# ADC.net
KiCad netlist of a schematic drawn in Altium Designer
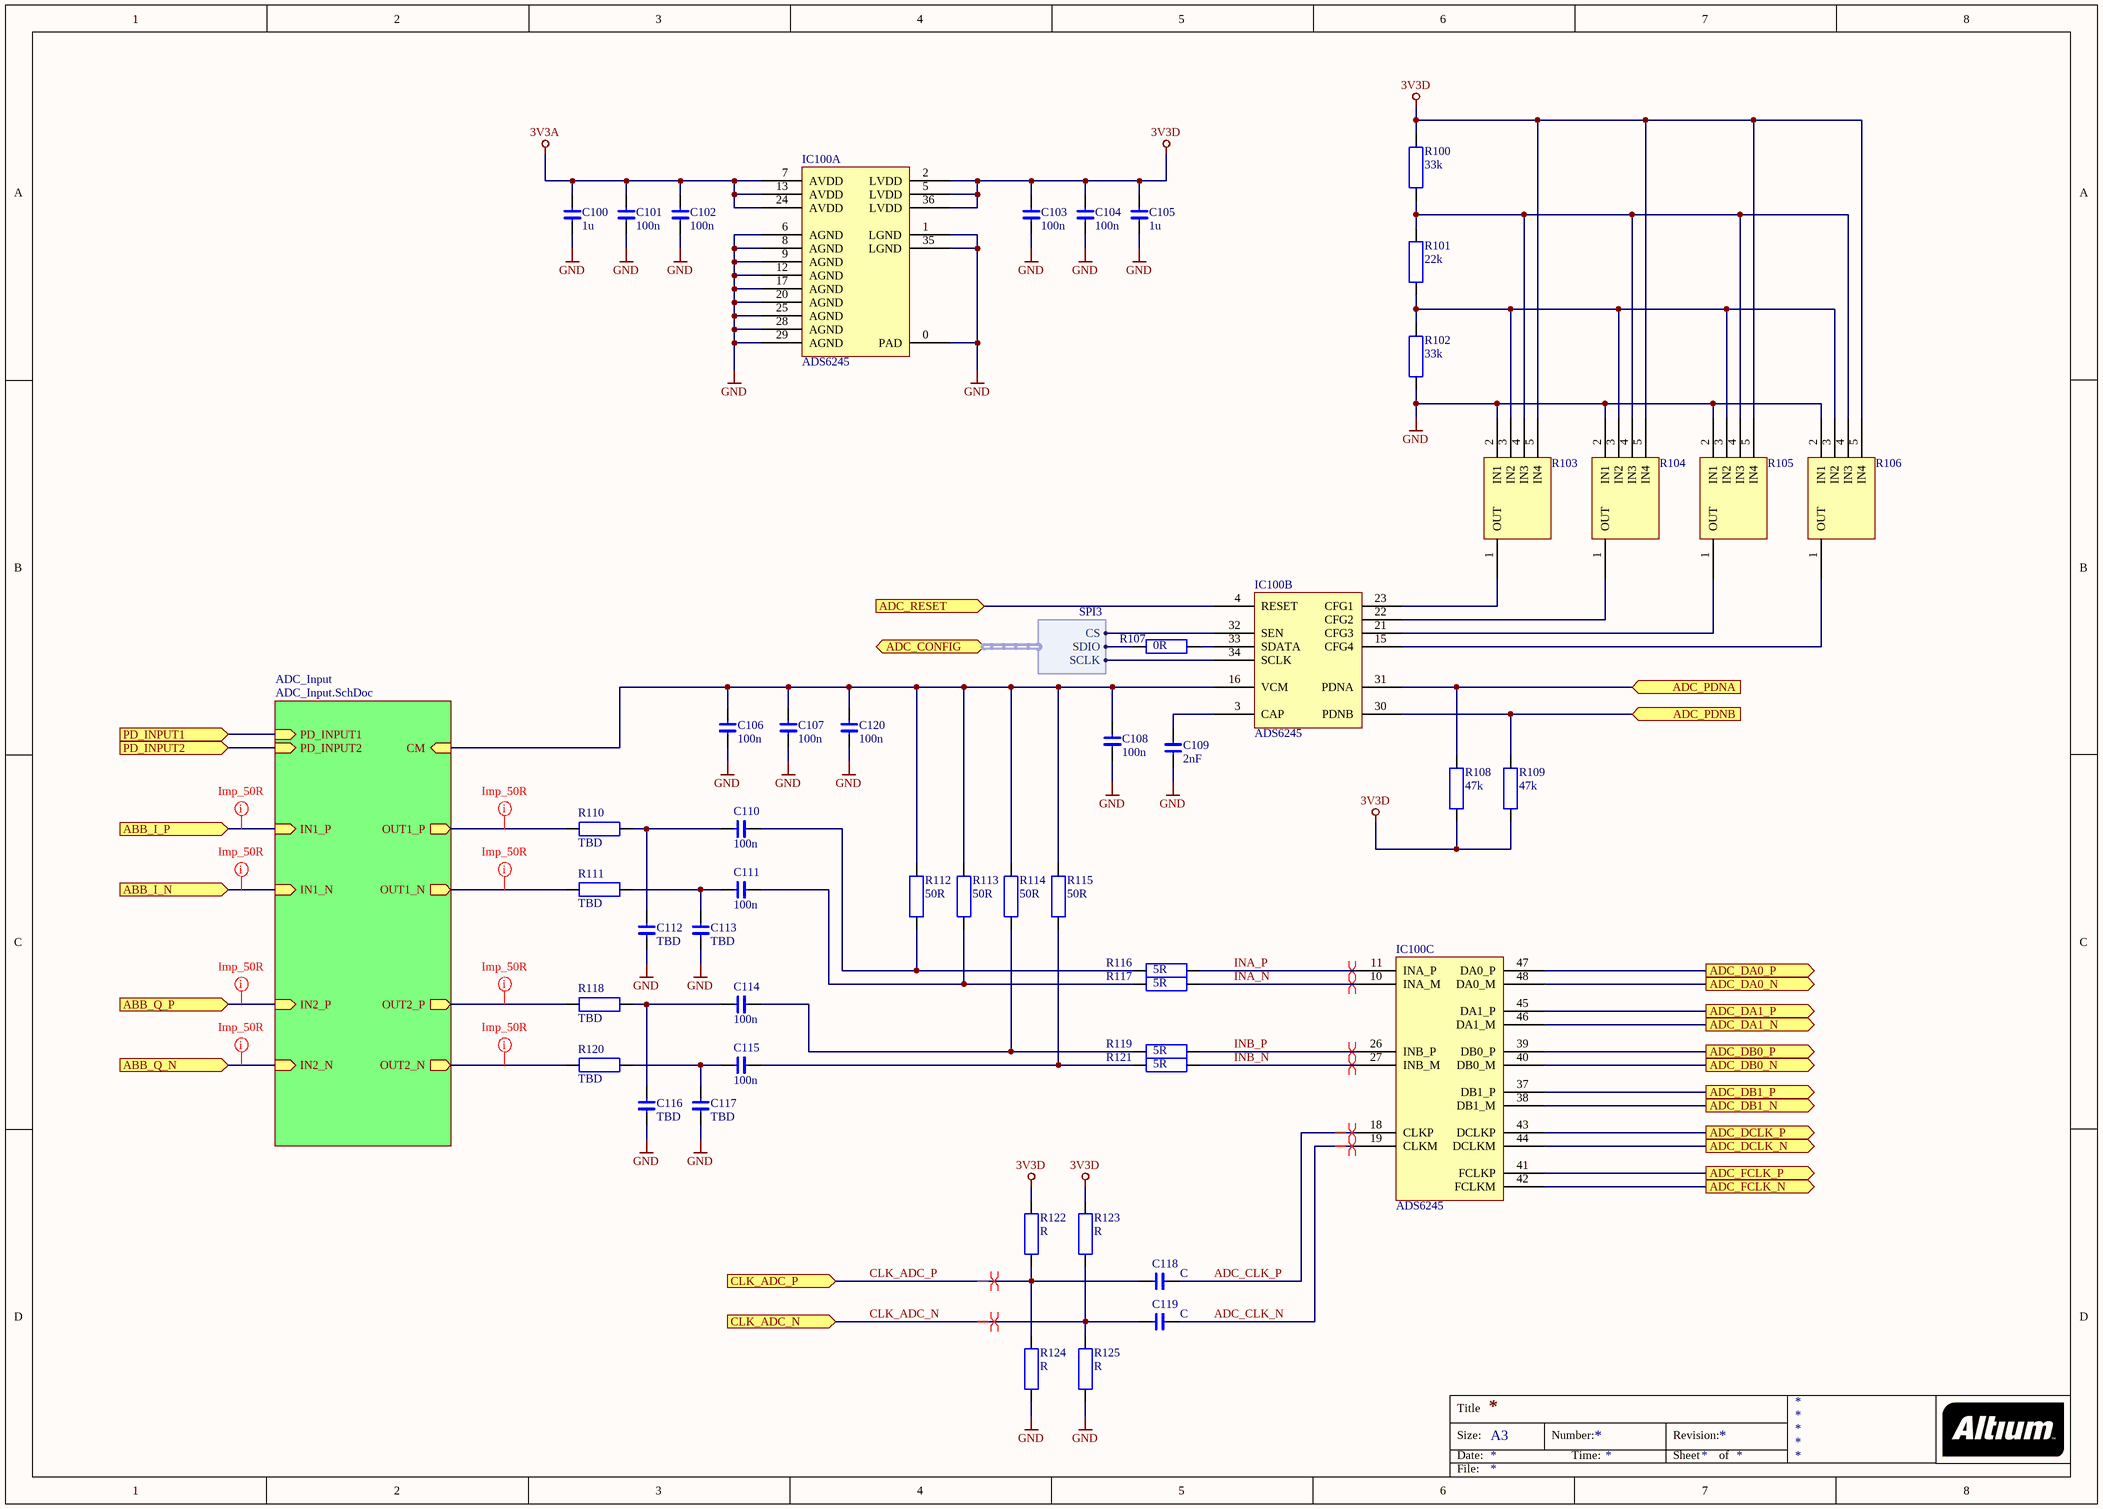
[diagram p0: ADC.SchDoc]

(export (version "E")
  (design (tool "Eeschema 10.0.6"))
  (components
    (comp (ref "C100")
      (value "1u")
      (footprint "0603 SMALL OUTLINE")
      (description "C")
      (libsource (lib "RCL") (part "C"))
    )
    (comp (ref "C101")
      (value "100n")
      (footprint "0603 SMALL OUTLINE")
      (description "C")
      (libsource (lib "RCL") (part "C"))
    )
    (comp (ref "C102")
      (value "100n")
      (footprint "0603 SMALL OUTLINE")
      (description "C")
      (libsource (lib "RCL") (part "C"))
    )
    (comp (ref "C103")
      (value "100n")
      (footprint "0603 SMALL OUTLINE")
      (description "C")
      (libsource (lib "RCL") (part "C"))
    )
    (comp (ref "C104")
      (value "100n")
      (footprint "0603 SMALL OUTLINE")
      (description "C")
      (libsource (lib "RCL") (part "C"))
    )
    (comp (ref "C105")
      (value "1u")
      (footprint "0603 SMALL OUTLINE")
      (description "C")
      (libsource (lib "RCL") (part "C"))
    )
    (comp (ref "C106")
      (value "100n")
      (footprint "0603 SMALL OUTLINE")
      (description "C")
      (libsource (lib "RCL") (part "C"))
    )
    (comp (ref "C107")
      (value "100n")
      (footprint "0603 SMALL OUTLINE")
      (description "C")
      (libsource (lib "RCL") (part "C"))
    )
    (comp (ref "C108")
      (value "100n")
      (footprint "0603 SMALL OUTLINE")
      (description "C")
      (libsource (lib "RCL") (part "C"))
    )
    (comp (ref "C109")
      (value "2nF")
      (footprint "0603 SMALL OUTLINE")
      (description "C")
      (libsource (lib "RCL") (part "C"))
    )
    (comp (ref "C110")
      (value "100n")
      (footprint "0603 SMALL OUTLINE")
      (description "C")
      (libsource (lib "RCL") (part "C"))
    )
    (comp (ref "C111")
      (value "100n")
      (footprint "0603 SMALL OUTLINE")
      (description "C")
      (libsource (lib "RCL") (part "C"))
    )
    (comp (ref "C112")
      (value "TBD")
      (footprint "0603 SMALL OUTLINE")
      (description "C")
      (libsource (lib "RCL") (part "C"))
    )
    (comp (ref "C113")
      (value "TBD")
      (footprint "0603 SMALL OUTLINE")
      (description "C")
      (libsource (lib "RCL") (part "C"))
    )
    (comp (ref "C114")
      (value "100n")
      (footprint "0603 SMALL OUTLINE")
      (description "C")
      (libsource (lib "RCL") (part "C"))
    )
    (comp (ref "C115")
      (value "100n")
      (footprint "0603 SMALL OUTLINE")
      (description "C")
      (libsource (lib "RCL") (part "C"))
    )
    (comp (ref "C116")
      (value "TBD")
      (footprint "0603 SMALL OUTLINE")
      (description "C")
      (libsource (lib "RCL") (part "C"))
    )
    (comp (ref "C117")
      (value "TBD")
      (footprint "0603 SMALL OUTLINE")
      (description "C")
      (libsource (lib "RCL") (part "C"))
    )
    (comp (ref "C118") (value "C") (footprint "0603 SMALL OUTLINE") (libsource (lib "RCL") (part "C")))
    (comp (ref "C119") (value "C") (footprint "0603 SMALL OUTLINE") (libsource (lib "RCL") (part "C")))
    (comp (ref "C120")
      (value "100n")
      (footprint "0603 SMALL OUTLINE")
      (description "C")
      (libsource (lib "RCL") (part "C"))
    )
    (comp (ref "IC100")
      (value "ADS6245")
      (footprint "VQFN48_LONG")
      (description "DUAL CHANNEL, 14-BIT, 125/105/80/65 MSPS ADC WITH SERIAL LVDS OUTPUTS")
      (libsource (lib "Private") (part "ADS6245_2WIRE"))
    )
    (comp (ref "R100")
      (value "33k")
      (footprint "0603 SMALL OUTLINE")
      (description "R")
      (libsource (lib "RCL") (part "R"))
    )
    (comp (ref "R101")
      (value "22k")
      (footprint "0603 SMALL OUTLINE")
      (description "R")
      (libsource (lib "RCL") (part "R"))
    )
    (comp (ref "R102")
      (value "33k")
      (footprint "0603 SMALL OUTLINE")
      (description "R")
      (libsource (lib "RCL") (part "R"))
    )
    (comp (ref "R103")
      (value "0603_MUX4")
      (footprint "0603_MUX4")
      (libsource (lib "Private") (part "0603_MUX4"))
    )
    (comp (ref "R104")
      (value "0603_MUX4")
      (footprint "0603_MUX4")
      (libsource (lib "Private") (part "0603_MUX4"))
    )
    (comp (ref "R105")
      (value "0603_MUX4")
      (footprint "0603_MUX4")
      (libsource (lib "Private") (part "0603_MUX4"))
    )
    (comp (ref "R106")
      (value "0603_MUX4")
      (footprint "0603_MUX4")
      (libsource (lib "Private") (part "0603_MUX4"))
    )
    (comp (ref "R107")
      (value "0R")
      (footprint "0603 SMALL OUTLINE")
      (description "R")
      (libsource (lib "RCL") (part "R"))
    )
    (comp (ref "R108")
      (value "47k")
      (footprint "0603 SMALL OUTLINE")
      (description "R")
      (libsource (lib "RCL") (part "R"))
    )
    (comp (ref "R109")
      (value "47k")
      (footprint "0603 SMALL OUTLINE")
      (description "R")
      (libsource (lib "RCL") (part "R"))
    )
    (comp (ref "R110")
      (value "TBD")
      (footprint "0603 SMALL OUTLINE")
      (description "R")
      (libsource (lib "RCL") (part "R"))
    )
    (comp (ref "R111")
      (value "TBD")
      (footprint "0603 SMALL OUTLINE")
      (description "R")
      (libsource (lib "RCL") (part "R"))
    )
    (comp (ref "R112")
      (value "50R")
      (footprint "0603 SMALL OUTLINE")
      (description "R")
      (libsource (lib "RCL") (part "R"))
    )
    (comp (ref "R113")
      (value "50R")
      (footprint "0603 SMALL OUTLINE")
      (description "R")
      (libsource (lib "RCL") (part "R"))
    )
    (comp (ref "R114")
      (value "50R")
      (footprint "0603 SMALL OUTLINE")
      (description "R")
      (libsource (lib "RCL") (part "R"))
    )
    (comp (ref "R115")
      (value "50R")
      (footprint "0603 SMALL OUTLINE")
      (description "R")
      (libsource (lib "RCL") (part "R"))
    )
    (comp (ref "R116")
      (value "5R")
      (footprint "0603 SMALL OUTLINE")
      (description "R")
      (libsource (lib "RCL") (part "R"))
    )
    (comp (ref "R117")
      (value "5R")
      (footprint "0603 SMALL OUTLINE")
      (description "R")
      (libsource (lib "RCL") (part "R"))
    )
    (comp (ref "R118")
      (value "TBD")
      (footprint "0603 SMALL OUTLINE")
      (description "R")
      (libsource (lib "RCL") (part "R"))
    )
    (comp (ref "R119")
      (value "5R")
      (footprint "0603 SMALL OUTLINE")
      (description "R")
      (libsource (lib "RCL") (part "R"))
    )
    (comp (ref "R120")
      (value "TBD")
      (footprint "0603 SMALL OUTLINE")
      (description "R")
      (libsource (lib "RCL") (part "R"))
    )
    (comp (ref "R121")
      (value "5R")
      (footprint "0603 SMALL OUTLINE")
      (description "R")
      (libsource (lib "RCL") (part "R"))
    )
    (comp (ref "R122") (value "R") (footprint "0603 SMALL OUTLINE") (libsource (lib "RCL") (part "R")))
    (comp (ref "R123") (value "R") (footprint "0603 SMALL OUTLINE") (libsource (lib "RCL") (part "R")))
    (comp (ref "R124") (value "R") (footprint "0603 SMALL OUTLINE") (libsource (lib "RCL") (part "R")))
    (comp (ref "R125") (value "R") (footprint "0603 SMALL OUTLINE") (libsource (lib "RCL") (part "R")))
  )
  (nets
    (net (code "6") (name "/ADC_CLK_N") (class "Default")
      (node (ref "C119") (pin "2") (pinfunction "2_2") (pintype "passive"))
      (node (ref "IC100") (pin "19") (pinfunction "CLKM_19") (pintype "passive"))
    )
    (net (code "7") (name "/ADC_CLK_P") (class "Default")
      (node (ref "C118") (pin "2") (pinfunction "2_2") (pintype "passive"))
      (node (ref "IC100") (pin "18") (pinfunction "CLKP_18") (pintype "passive"))
    )
    (net (code "8") (name "/ADC_DA0_N") (class "Default")
      (node (ref "IC100") (pin "48") (pinfunction "DA0_M_48") (pintype "passive"))
    )
    (net (code "9") (name "/ADC_DA0_P") (class "Default")
      (node (ref "IC100") (pin "47") (pinfunction "DA0_P_47") (pintype "passive"))
    )
    (net (code "10") (name "/ADC_DA1_N") (class "Default")
      (node (ref "IC100") (pin "46") (pinfunction "DA1_M_46") (pintype "passive"))
    )
    (net (code "11") (name "/ADC_DA1_P") (class "Default")
      (node (ref "IC100") (pin "45") (pinfunction "DA1_P_45") (pintype "passive"))
    )
    (net (code "12") (name "/ADC_DB0_N") (class "Default")
      (node (ref "IC100") (pin "40") (pinfunction "DB0_M_40") (pintype "passive"))
    )
    (net (code "13") (name "/ADC_DB0_P") (class "Default")
      (node (ref "IC100") (pin "39") (pinfunction "DB0_P_39") (pintype "passive"))
    )
    (net (code "14") (name "/ADC_DB1_N") (class "Default")
      (node (ref "IC100") (pin "38") (pinfunction "DB1_M_38") (pintype "passive"))
    )
    (net (code "15") (name "/ADC_DB1_P") (class "Default")
      (node (ref "IC100") (pin "37") (pinfunction "DB1_P_37") (pintype "passive"))
    )
    (net (code "16") (name "/ADC_DCLK_N") (class "Default")
      (node (ref "IC100") (pin "44") (pinfunction "DCLKM_44") (pintype "passive"))
    )
    (net (code "17") (name "/ADC_DCLK_P") (class "Default")
      (node (ref "IC100") (pin "43") (pinfunction "DCLKP_43") (pintype "passive"))
    )
    (net (code "18") (name "/ADC_FCLK_N") (class "Default")
      (node (ref "IC100") (pin "42") (pinfunction "FCLKM_42") (pintype "passive"))
    )
    (net (code "19") (name "/ADC_FCLK_P") (class "Default")
      (node (ref "IC100") (pin "41") (pinfunction "FCLKP_41") (pintype "passive"))
    )
    (net (code "20") (name "/ADC_PDNA") (class "Default")
      (node (ref "IC100") (pin "31") (pinfunction "PDNA_31") (pintype "passive"))
      (node (ref "R108") (pin "2") (pinfunction "2_2") (pintype "passive"))
    )
    (net (code "21") (name "/ADC_PDNB") (class "Default")
      (node (ref "IC100") (pin "30") (pinfunction "PDNB_30") (pintype "passive"))
      (node (ref "R109") (pin "2") (pinfunction "2_2") (pintype "passive"))
    )
    (net (code "22") (name "/ADC_RESET") (class "Default")
      (node (ref "IC100") (pin "4") (pinfunction "RESET_4") (pintype "passive"))
    )
    (net (code "23") (name "/CLK_ADC_N") (class "Default")
      (node (ref "C119") (pin "1") (pinfunction "1_1") (pintype "passive"))
      (node (ref "R123") (pin "2") (pinfunction "2_2") (pintype "passive"))
      (node (ref "R125") (pin "1") (pinfunction "1_1") (pintype "passive"))
    )
    (net (code "24") (name "/CLK_ADC_P") (class "Default")
      (node (ref "C118") (pin "1") (pinfunction "1_1") (pintype "passive"))
      (node (ref "R122") (pin "2") (pinfunction "2_2") (pintype "passive"))
      (node (ref "R124") (pin "1") (pinfunction "1_1") (pintype "passive"))
    )
    (net (code "25") (name "/CM") (class "Default")
      (node (ref "C106") (pin "1") (pinfunction "1_1") (pintype "passive"))
      (node (ref "C107") (pin "1") (pinfunction "1_1") (pintype "passive"))
      (node (ref "C108") (pin "1") (pinfunction "1_1") (pintype "passive"))
      (node (ref "C120") (pin "1") (pinfunction "1_1") (pintype "passive"))
      (node (ref "IC100") (pin "16") (pinfunction "VCM_16") (pintype "passive"))
      (node (ref "R112") (pin "1") (pinfunction "1_1") (pintype "passive"))
      (node (ref "R113") (pin "1") (pinfunction "1_1") (pintype "passive"))
      (node (ref "R114") (pin "1") (pinfunction "1_1") (pintype "passive"))
      (node (ref "R115") (pin "1") (pinfunction "1_1") (pintype "passive"))
    )
    (net (code "26") (name "/CS") (class "Default")
      (node (ref "IC100") (pin "32") (pinfunction "SEN_32") (pintype "passive"))
    )
    (net (code "27") (name "/INA_N") (class "Default")
      (node (ref "IC100") (pin "10") (pinfunction "INA_M_10") (pintype "passive"))
      (node (ref "R117") (pin "2") (pinfunction "2_2") (pintype "passive"))
    )
    (net (code "28") (name "/INA_P") (class "Default")
      (node (ref "IC100") (pin "11") (pinfunction "INA_P_11") (pintype "passive"))
      (node (ref "R116") (pin "2") (pinfunction "2_2") (pintype "passive"))
    )
    (net (code "29") (name "/INB_N") (class "Default")
      (node (ref "IC100") (pin "27") (pinfunction "INB_M_27") (pintype "passive"))
      (node (ref "R121") (pin "2") (pinfunction "2_2") (pintype "passive"))
    )
    (net (code "30") (name "/INB_P") (class "Default")
      (node (ref "IC100") (pin "26") (pinfunction "INB_P_26") (pintype "passive"))
      (node (ref "R119") (pin "2") (pinfunction "2_2") (pintype "passive"))
    )
    (net (code "31") (name "/OUT1_N") (class "Default")
      (node (ref "R111") (pin "2") (pinfunction "2_2") (pintype "passive"))
    )
    (net (code "32") (name "/OUT1_P") (class "Default")
      (node (ref "R110") (pin "2") (pinfunction "2_2") (pintype "passive"))
    )
    (net (code "33") (name "/OUT2_N") (class "Default")
      (node (ref "R120") (pin "2") (pinfunction "2_2") (pintype "passive"))
    )
    (net (code "34") (name "/OUT2_P") (class "Default")
      (node (ref "R118") (pin "2") (pinfunction "2_2") (pintype "passive"))
    )
    (net (code "37") (name "/SCLK") (class "Default")
      (node (ref "IC100") (pin "34") (pinfunction "SCLK_34") (pintype "passive"))
    )
    (net (code "38") (name "/SDIO") (class "Default")
      (node (ref "R107") (pin "1") (pinfunction "1_1") (pintype "passive"))
    )
    (net (code "40") (name "3V3A") (class "Default")
      (node (ref "C100") (pin "1") (pinfunction "1_1") (pintype "passive"))
      (node (ref "C101") (pin "1") (pinfunction "1_1") (pintype "passive"))
      (node (ref "C102") (pin "1") (pinfunction "1_1") (pintype "passive"))
      (node (ref "IC100") (pin "13") (pinfunction "AVDD_13") (pintype "passive"))
      (node (ref "IC100") (pin "24") (pinfunction "AVDD_24") (pintype "passive"))
      (node (ref "IC100") (pin "7") (pinfunction "AVDD_7") (pintype "passive"))
    )
    (net (code "41") (name "3V3D") (class "Default")
      (node (ref "C103") (pin "1") (pinfunction "1_1") (pintype "passive"))
      (node (ref "C104") (pin "1") (pinfunction "1_1") (pintype "passive"))
      (node (ref "C105") (pin "1") (pinfunction "1_1") (pintype "passive"))
      (node (ref "IC100") (pin "2") (pinfunction "LVDD_2") (pintype "passive"))
      (node (ref "IC100") (pin "36") (pinfunction "LVDD_36") (pintype "passive"))
      (node (ref "IC100") (pin "5") (pinfunction "LVDD_5") (pintype "passive"))
      (node (ref "R100") (pin "2") (pinfunction "2_2") (pintype "passive"))
      (node (ref "R103") (pin "5") (pinfunction "IN4_5") (pintype "passive"))
      (node (ref "R104") (pin "5") (pinfunction "IN4_5") (pintype "passive"))
      (node (ref "R105") (pin "5") (pinfunction "IN4_5") (pintype "passive"))
      (node (ref "R106") (pin "5") (pinfunction "IN4_5") (pintype "passive"))
      (node (ref "R108") (pin "1") (pinfunction "1_1") (pintype "passive"))
      (node (ref "R109") (pin "1") (pinfunction "1_1") (pintype "passive"))
      (node (ref "R122") (pin "1") (pinfunction "1_1") (pintype "passive"))
      (node (ref "R123") (pin "1") (pinfunction "1_1") (pintype "passive"))
    )
    (net (code "42") (name "GND") (class "Default")
      (node (ref "C100") (pin "2") (pinfunction "2_2") (pintype "passive"))
      (node (ref "C101") (pin "2") (pinfunction "2_2") (pintype "passive"))
      (node (ref "C102") (pin "2") (pinfunction "2_2") (pintype "passive"))
      (node (ref "C103") (pin "2") (pinfunction "2_2") (pintype "passive"))
      (node (ref "C104") (pin "2") (pinfunction "2_2") (pintype "passive"))
      (node (ref "C105") (pin "2") (pinfunction "2_2") (pintype "passive"))
      (node (ref "C106") (pin "2") (pinfunction "2_2") (pintype "passive"))
      (node (ref "C107") (pin "2") (pinfunction "2_2") (pintype "passive"))
      (node (ref "C108") (pin "2") (pinfunction "2_2") (pintype "passive"))
      (node (ref "C109") (pin "2") (pinfunction "2_2") (pintype "passive"))
      (node (ref "C112") (pin "2") (pinfunction "2_2") (pintype "passive"))
      (node (ref "C113") (pin "2") (pinfunction "2_2") (pintype "passive"))
      (node (ref "C116") (pin "2") (pinfunction "2_2") (pintype "passive"))
      (node (ref "C117") (pin "2") (pinfunction "2_2") (pintype "passive"))
      (node (ref "C120") (pin "2") (pinfunction "2_2") (pintype "passive"))
      (node (ref "IC100") (pin "0") (pinfunction "PAD_0") (pintype "passive"))
      (node (ref "IC100") (pin "1") (pinfunction "LGND_1") (pintype "passive"))
      (node (ref "IC100") (pin "12") (pinfunction "AGND_12") (pintype "passive"))
      (node (ref "IC100") (pin "17") (pinfunction "AGND_17") (pintype "passive"))
      (node (ref "IC100") (pin "20") (pinfunction "AGND_20") (pintype "passive"))
      (node (ref "IC100") (pin "25") (pinfunction "AGND_25") (pintype "passive"))
      (node (ref "IC100") (pin "28") (pinfunction "AGND_28") (pintype "passive"))
      (node (ref "IC100") (pin "29") (pinfunction "AGND_29") (pintype "passive"))
      (node (ref "IC100") (pin "35") (pinfunction "LGND_35") (pintype "passive"))
      (node (ref "IC100") (pin "6") (pinfunction "AGND_6") (pintype "passive"))
      (node (ref "IC100") (pin "8") (pinfunction "AGND_8") (pintype "passive"))
      (node (ref "IC100") (pin "9") (pinfunction "AGND_9") (pintype "passive"))
      (node (ref "R102") (pin "1") (pinfunction "1_1") (pintype "passive"))
      (node (ref "R103") (pin "2") (pinfunction "IN1_2") (pintype "passive"))
      (node (ref "R104") (pin "2") (pinfunction "IN1_2") (pintype "passive"))
      (node (ref "R105") (pin "2") (pinfunction "IN1_2") (pintype "passive"))
      (node (ref "R106") (pin "2") (pinfunction "IN1_2") (pintype "passive"))
      (node (ref "R124") (pin "2") (pinfunction "2_2") (pintype "passive"))
      (node (ref "R125") (pin "2") (pinfunction "2_2") (pintype "passive"))
    )
    (net (code "43") (name "Net-(C110-Pad1)") (class "Default")
      (node (ref "C110") (pin "1") (pinfunction "1_1") (pintype "passive"))
      (node (ref "R112") (pin "2") (pinfunction "2_2") (pintype "passive"))
      (node (ref "R116") (pin "1") (pinfunction "1_1") (pintype "passive"))
    )
    (net (code "44") (name "Net-(C110-Pad2)") (class "Default")
      (node (ref "C110") (pin "2") (pinfunction "2_2") (pintype "passive"))
      (node (ref "C112") (pin "1") (pinfunction "1_1") (pintype "passive"))
      (node (ref "R110") (pin "1") (pinfunction "1_1") (pintype "passive"))
    )
    (net (code "45") (name "Net-(C111-Pad1)") (class "Default")
      (node (ref "C111") (pin "1") (pinfunction "1_1") (pintype "passive"))
      (node (ref "R113") (pin "2") (pinfunction "2_2") (pintype "passive"))
      (node (ref "R117") (pin "1") (pinfunction "1_1") (pintype "passive"))
    )
    (net (code "46") (name "Net-(C111-Pad2)") (class "Default")
      (node (ref "C111") (pin "2") (pinfunction "2_2") (pintype "passive"))
      (node (ref "C113") (pin "1") (pinfunction "1_1") (pintype "passive"))
      (node (ref "R111") (pin "1") (pinfunction "1_1") (pintype "passive"))
    )
    (net (code "47") (name "Net-(C114-Pad1)") (class "Default")
      (node (ref "C114") (pin "1") (pinfunction "1_1") (pintype "passive"))
      (node (ref "R114") (pin "2") (pinfunction "2_2") (pintype "passive"))
      (node (ref "R119") (pin "1") (pinfunction "1_1") (pintype "passive"))
    )
    (net (code "48") (name "Net-(C114-Pad2)") (class "Default")
      (node (ref "C114") (pin "2") (pinfunction "2_2") (pintype "passive"))
      (node (ref "C116") (pin "1") (pinfunction "1_1") (pintype "passive"))
      (node (ref "R118") (pin "1") (pinfunction "1_1") (pintype "passive"))
    )
    (net (code "49") (name "Net-(C115-Pad1)") (class "Default")
      (node (ref "C115") (pin "1") (pinfunction "1_1") (pintype "passive"))
      (node (ref "R115") (pin "2") (pinfunction "2_2") (pintype "passive"))
      (node (ref "R121") (pin "1") (pinfunction "1_1") (pintype "passive"))
    )
    (net (code "50") (name "Net-(C115-Pad2)") (class "Default")
      (node (ref "C115") (pin "2") (pinfunction "2_2") (pintype "passive"))
      (node (ref "C117") (pin "1") (pinfunction "1_1") (pintype "passive"))
      (node (ref "R120") (pin "1") (pinfunction "1_1") (pintype "passive"))
    )
    (net (code "51") (name "Net-(IC100B-CAP)") (class "Default")
      (node (ref "C109") (pin "1") (pinfunction "1_1") (pintype "passive"))
      (node (ref "IC100") (pin "3") (pinfunction "CAP_3") (pintype "passive"))
    )
    (net (code "52") (name "Net-(IC100B-CFG1)") (class "Default")
      (node (ref "IC100") (pin "23") (pinfunction "CFG1_23") (pintype "passive"))
      (node (ref "R103") (pin "1") (pinfunction "OUT_1") (pintype "passive"))
    )
    (net (code "53") (name "Net-(IC100B-CFG2)") (class "Default")
      (node (ref "IC100") (pin "22") (pinfunction "CFG2_22") (pintype "passive"))
      (node (ref "R104") (pin "1") (pinfunction "OUT_1") (pintype "passive"))
    )
    (net (code "54") (name "Net-(IC100B-CFG3)") (class "Default")
      (node (ref "IC100") (pin "21") (pinfunction "CFG3_21") (pintype "passive"))
      (node (ref "R105") (pin "1") (pinfunction "OUT_1") (pintype "passive"))
    )
    (net (code "55") (name "Net-(IC100B-CFG4)") (class "Default")
      (node (ref "IC100") (pin "15") (pinfunction "CFG4_15") (pintype "passive"))
      (node (ref "R106") (pin "1") (pinfunction "OUT_1") (pintype "passive"))
    )
    (net (code "56") (name "Net-(IC100B-SDATA)") (class "Default")
      (node (ref "IC100") (pin "33") (pinfunction "SDATA_33") (pintype "passive"))
      (node (ref "R107") (pin "2") (pinfunction "2_2") (pintype "passive"))
    )
    (net (code "57") (name "Net-(R103-IN2)") (class "Default")
      (node (ref "R101") (pin "1") (pinfunction "1_1") (pintype "passive"))
      (node (ref "R102") (pin "2") (pinfunction "2_2") (pintype "passive"))
      (node (ref "R103") (pin "3") (pinfunction "IN2_3") (pintype "passive"))
      (node (ref "R104") (pin "3") (pinfunction "IN2_3") (pintype "passive"))
      (node (ref "R105") (pin "3") (pinfunction "IN2_3") (pintype "passive"))
      (node (ref "R106") (pin "3") (pinfunction "IN2_3") (pintype "passive"))
    )
    (net (code "58") (name "Net-(R103-IN3)") (class "Default")
      (node (ref "R100") (pin "1") (pinfunction "1_1") (pintype "passive"))
      (node (ref "R101") (pin "2") (pinfunction "2_2") (pintype "passive"))
      (node (ref "R103") (pin "4") (pinfunction "IN3_4") (pintype "passive"))
      (node (ref "R104") (pin "4") (pinfunction "IN3_4") (pintype "passive"))
      (node (ref "R105") (pin "4") (pinfunction "IN3_4") (pintype "passive"))
      (node (ref "R106") (pin "4") (pinfunction "IN3_4") (pintype "passive"))
    )
  )
)
